# Desktop_Widget.net
KiCad netlist of a schematic drawn in EAGLE
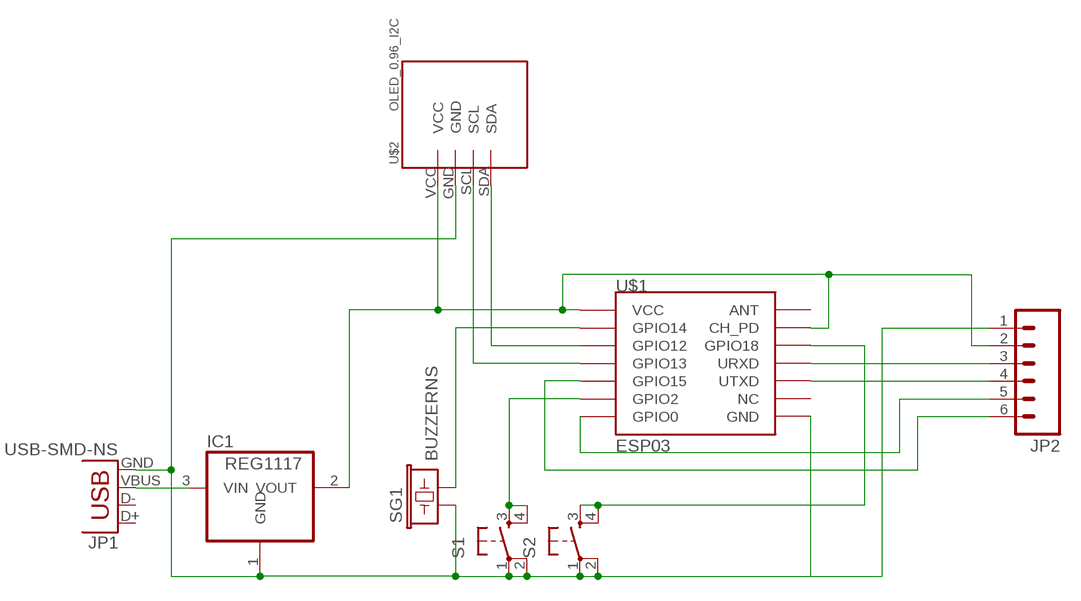
[diagram p0: schematic, sheet 1]

(export (version "E")
  (design (tool "Eeschema 10.0.6"))
  (components
    (comp (ref "IC1")
      (value "REG1117")
      (footprint "eagle-import:SOT223")
      (libsource (lib "eagle-import") (part "REG1117"))
    )
    (comp (ref "JP1")
      (value "USB-SMD-NS")
      (footprint "eagle-import:USB-MINIB-NOSTOP")
      (libsource (lib "eagle-import") (part "USB-SMD-NS"))
    )
    (comp (ref "JP2")
      (value "M06SILK_FEMALE_PTH")
      (footprint "eagle-import:1X06")
      (libsource (lib "eagle-import") (part "M06SILK_FEMALE_PTH"))
    )
    (comp (ref "S1")
      (value "TAC_SWITCHPTH")
      (footprint "eagle-import:TACTILE-PTH")
      (libsource (lib "eagle-import") (part "TAC_SWITCHPTH"))
    )
    (comp (ref "S2")
      (value "TAC_SWITCHPTH")
      (footprint "eagle-import:TACTILE-PTH")
      (libsource (lib "eagle-import") (part "TAC_SWITCHPTH"))
    )
    (comp (ref "SG1")
      (value "BUZZERNS")
      (footprint "eagle-import:BUZZER-12MM-NS")
      (libsource (lib "eagle-import") (part "BUZZERNS"))
    )
    (comp (ref "U$1")
      (value "ESP03")
      (footprint "eagle-import:ESP03")
      (libsource (lib "eagle-import") (part "ESP03"))
    )
    (comp (ref "U$2")
      (value "OLED_0.96_I2C")
      (footprint "eagle-import:OLED_0.96_I2C")
      (libsource (lib "eagle-import") (part "OLED_0.96_I2C"))
    )
  )
  (nets
    (net (code "1") (name "Net-(IC1-GND)") (class "Default")
      (node (ref "IC1") (pin "1") (pinfunction "GND_1") (pintype "power_in"))
      (node (ref "JP1") (pin "GND") (pinfunction "GND_GND") (pintype "bidirectional"))
      (node (ref "JP2") (pin "1") (pinfunction "1_1") (pintype "passive"))
      (node (ref "S1") (pin "1") (pinfunction "1_1") (pintype "passive"))
      (node (ref "S1") (pin "2") (pinfunction "2_2") (pintype "passive"))
      (node (ref "S2") (pin "1") (pinfunction "1_1") (pintype "passive"))
      (node (ref "S2") (pin "2") (pinfunction "2_2") (pintype "passive"))
      (node (ref "SG1") (pin "+") (pinfunction "1_+") (pintype "passive"))
      (node (ref "U$1") (pin "GND") (pinfunction "GND_GND") (pintype "bidirectional"))
      (node (ref "U$2") (pin "GND") (pinfunction "GND_GND") (pintype "bidirectional"))
    )
    (net (code "2") (name "Net-(IC1-VOUT)") (class "Default")
      (node (ref "IC1") (pin "2") (pinfunction "VOUT_2") (pintype "output"))
      (node (ref "JP2") (pin "2") (pinfunction "2_2") (pintype "passive"))
      (node (ref "U$1") (pin "CH_PD") (pinfunction "CH_PD_CH_PD") (pintype "bidirectional"))
      (node (ref "U$1") (pin "VCC") (pinfunction "VCC_VCC") (pintype "bidirectional"))
      (node (ref "U$2") (pin "VCC") (pinfunction "VCC_VCC") (pintype "bidirectional"))
    )
    (net (code "3") (name "Net-(JP2-Pad3)") (class "Default")
      (node (ref "JP2") (pin "3") (pinfunction "3_3") (pintype "passive"))
      (node (ref "U$1") (pin "URXD") (pinfunction "URXD_URXD") (pintype "bidirectional"))
    )
    (net (code "4") (name "Net-(JP2-Pad4)") (class "Default")
      (node (ref "JP2") (pin "4") (pinfunction "4_4") (pintype "passive"))
      (node (ref "U$1") (pin "UTXD") (pinfunction "UTXD_UTXD") (pintype "bidirectional"))
    )
    (net (code "5") (name "Net-(JP2-Pad5)") (class "Default")
      (node (ref "JP2") (pin "5") (pinfunction "5_5") (pintype "passive"))
      (node (ref "U$1") (pin "GPIO0") (pinfunction "GPIO0_GPIO0") (pintype "bidirectional"))
    )
    (net (code "6") (name "Net-(JP2-Pad6)") (class "Default")
      (node (ref "JP2") (pin "6") (pinfunction "6_6") (pintype "passive"))
      (node (ref "U$1") (pin "GPIO15") (pinfunction "GPIO15_GPIO15") (pintype "bidirectional"))
    )
    (net (code "7") (name "Net-(S1-Pad3)") (class "Default")
      (node (ref "S1") (pin "3") (pinfunction "3_3") (pintype "passive"))
      (node (ref "S1") (pin "4") (pinfunction "4_4") (pintype "passive"))
      (node (ref "U$1") (pin "GPIO2") (pinfunction "GPIO2_GPIO2") (pintype "bidirectional"))
    )
    (net (code "8") (name "Net-(S2-Pad3)") (class "Default")
      (node (ref "S2") (pin "3") (pinfunction "3_3") (pintype "passive"))
      (node (ref "S2") (pin "4") (pinfunction "4_4") (pintype "passive"))
      (node (ref "U$1") (pin "GPIO18") (pinfunction "GPIO18_GPIO18") (pintype "bidirectional"))
    )
    (net (code "9") (name "Net-(SG1-2)") (class "Default")
      (node (ref "SG1") (pin "-") (pinfunction "2_-") (pintype "passive"))
      (node (ref "U$1") (pin "GPIO14") (pinfunction "GPIO14_GPIO14") (pintype "bidirectional"))
    )
    (net (code "10") (name "Net-(U$1-PadGPIO12)") (class "Default")
      (node (ref "U$1") (pin "GPIO12") (pinfunction "GPIO12_GPIO12") (pintype "bidirectional"))
      (node (ref "U$2") (pin "SDA") (pinfunction "SDA_SDA") (pintype "bidirectional"))
    )
    (net (code "11") (name "Net-(U$1-PadGPIO13)") (class "Default")
      (node (ref "U$1") (pin "GPIO13") (pinfunction "GPIO13_GPIO13") (pintype "bidirectional"))
      (node (ref "U$2") (pin "SCL") (pinfunction "SCL_SCL") (pintype "bidirectional"))
    )
    (net (code "12") (name "unconnected-(IC1-VIN-Pad3)") (class "Default")
      (node (ref "IC1") (pin "3") (pinfunction "VIN_3") (pintype "input"))
    )
    (net (code "13") (name "unconnected-(JP1-PadD+)") (class "Default")
      (node (ref "JP1") (pin "D+") (pinfunction "D+_D+") (pintype "bidirectional"))
    )
    (net (code "14") (name "unconnected-(JP1-PadD-)") (class "Default")
      (node (ref "JP1") (pin "D-") (pinfunction "D-_D-") (pintype "bidirectional"))
    )
    (net (code "15") (name "unconnected-(JP1-PadVBUS)") (class "Default")
      (node (ref "JP1") (pin "VBUS") (pinfunction "VBUS_VBUS") (pintype "bidirectional"))
    )
    (net (code "16") (name "unconnected-(U$1-PadANT)") (class "Default")
      (node (ref "U$1") (pin "ANT") (pinfunction "ANT_ANT") (pintype "bidirectional"))
    )
    (net (code "17") (name "unconnected-(U$1-PadNC)") (class "Default")
      (node (ref "U$1") (pin "NC") (pinfunction "NC_NC") (pintype "bidirectional"))
    )
  )
)
